# msp430g2553o.net
KiCad netlist of a schematic drawn in Altium Designer
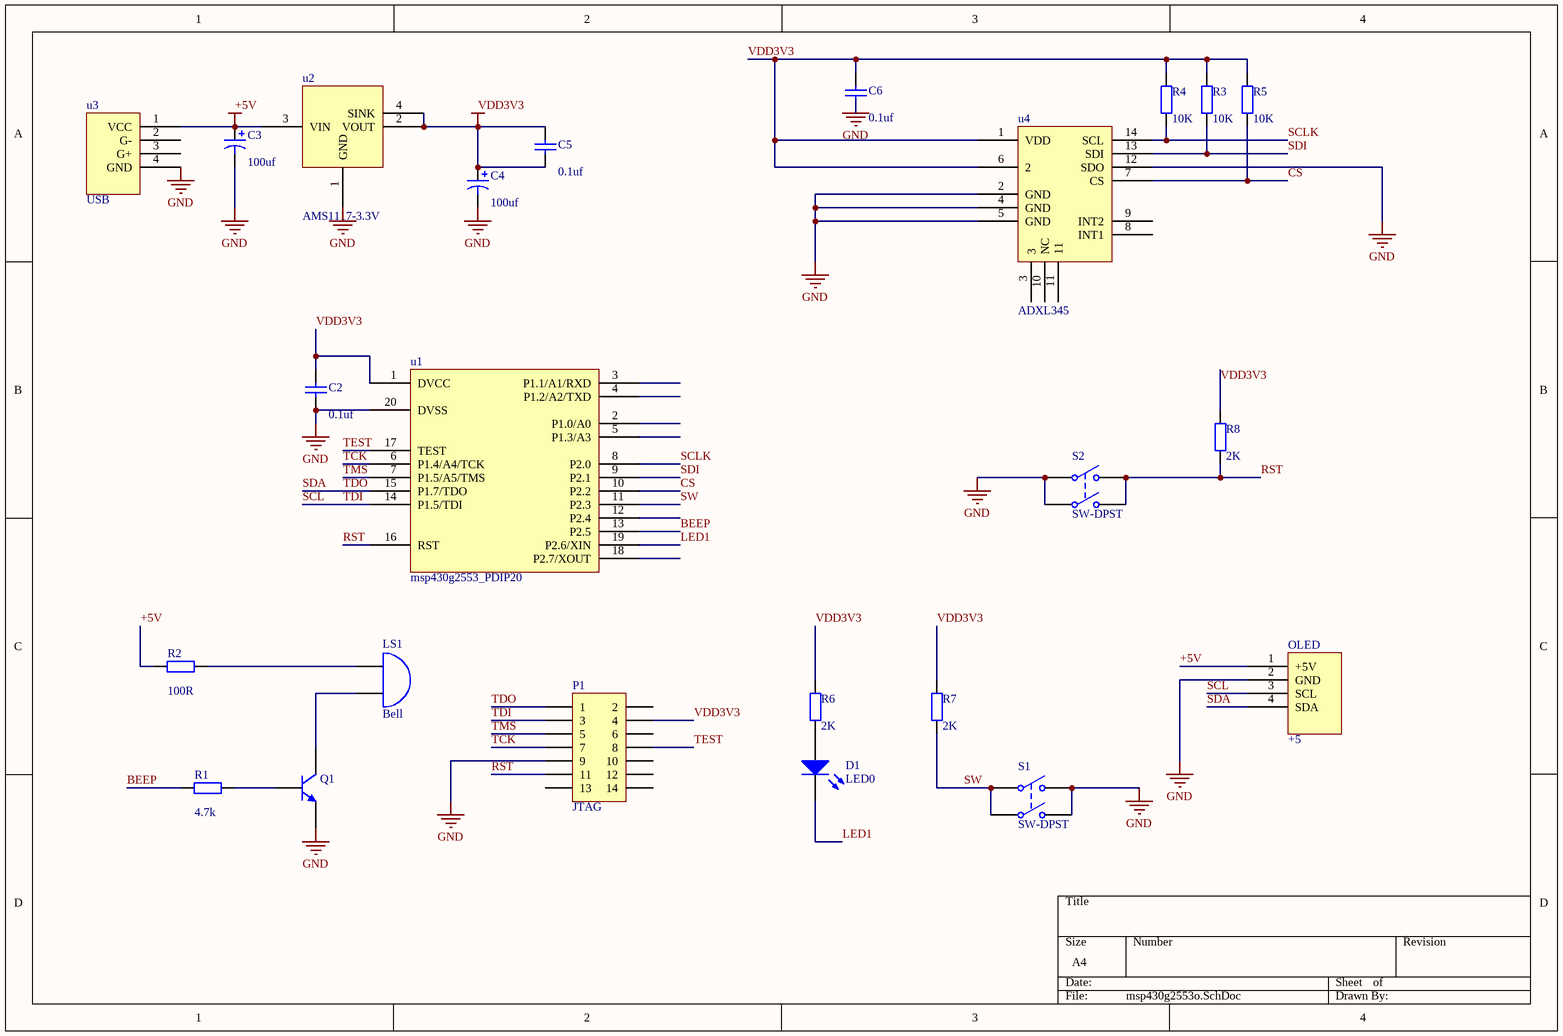
[diagram p0: msp430g2553o.SchDoc]

(export (version "E")
  (design (tool "Eeschema 10.0.6"))
  (components
    (comp (ref "C2")
      (value "0.1uf")
      (footprint "6-0805_N")
      (description "Capacitor")
      (fields (field (name "Comment") "Cap") (field (name "PUBLISHER") "Altium Limited"))
      (libsource (lib "msp430g2553") (part "Cap"))
    )
    (comp (ref "C3")
      (value "100uf")
      (footprint "Cap2_polar")
      (description "Polarized Capacitor (Axial)")
      (fields (field (name "Comment") "Cap Pol2") (field (name "PUBLISHER") "Altium Limited"))
      (libsource (lib "msp430g2553") (part "Cap Pol2"))
    )
    (comp (ref "C4")
      (value "100uf")
      (footprint "Cap2_polar")
      (description "Polarized Capacitor (Axial)")
      (fields (field (name "Comment") "Cap Pol2") (field (name "PUBLISHER") "Altium Limited"))
      (libsource (lib "msp430g2553") (part "Cap Pol2"))
    )
    (comp (ref "C5")
      (value "0.1uf")
      (footprint "6-0805_N")
      (description "Capacitor")
      (fields (field (name "Comment") "Cap") (field (name "PUBLISHER") "Altium Limited"))
      (libsource (lib "msp430g2553") (part "Cap"))
    )
    (comp (ref "C6")
      (value "0.1uf")
      (footprint "6-0805_N")
      (description "Capacitor")
      (fields (field (name "Comment") "Cap") (field (name "PUBLISHER") "Altium Limited"))
      (libsource (lib "msp430g2553") (part "Cap"))
    )
    (comp (ref "D1")
      (value "LED0")
      (footprint "6-0805_N - duplicate")
      (description "Typical INFRARED GaAs LED")
      (fields (field (name "PUBLISHER") "Altium Limited"))
      (libsource (lib "msp430g2553") (part "LED0"))
    )
    (comp (ref "LS1")
      (value "Bell")
      (footprint "bell")
      (description "Electrical Bell")
      (fields (field (name "PUBLISHER") "Altium Limited"))
      (libsource (lib "msp430g2553") (part "Bell"))
    )
    (comp (ref "OLED") (value "+5") (footprint "OLED") (libsource (lib "msp430g2553") (part "OLED")))
    (comp (ref "P1")
      (value "JTAG")
      (footprint "HDR2X7H")
      (description "Header, 7-Pin, Dual row")
      (fields (field (name "PUBLISHER") "Altium Limited"))
      (libsource (lib "msp430g2553") (part "JTAG"))
    )
    (comp (ref "Q1")
      (value "NPN")
      (footprint "SOT23_N")
      (description "NPN Bipolar Transistor")
      (fields (field (name "PUBLISHER") "Altium Limited"))
      (libsource (lib "msp430g2553") (part "NPN"))
    )
    (comp (ref "R1")
      (value "4.7k")
      (footprint "6-0805_N")
      (description "Resistor")
      (fields (field (name "Comment") "Res2") (field (name "PUBLISHER") "Altium Limited"))
      (libsource (lib "") (part "Res2_1"))
    )
    (comp (ref "R2")
      (value "100R")
      (footprint "6-0805_N")
      (description "Resistor")
      (fields (field (name "Comment") "Res2") (field (name "PUBLISHER") "Altium Limited"))
      (libsource (lib "") (part "Res2_1"))
    )
    (comp (ref "R3")
      (value "10K")
      (footprint "6-0805_N")
      (description "Resistor")
      (fields (field (name "Comment") "Res2") (field (name "PUBLISHER") "Altium Limited"))
      (libsource (lib "msp430g2553") (part "Res2"))
    )
    (comp (ref "R4")
      (value "10K")
      (footprint "6-0805_N")
      (description "Resistor")
      (fields (field (name "Comment") "Res2") (field (name "PUBLISHER") "Altium Limited"))
      (libsource (lib "msp430g2553") (part "Res2"))
    )
    (comp (ref "R5")
      (value "10K")
      (footprint "6-0805_N")
      (description "Resistor")
      (fields (field (name "Comment") "Res2") (field (name "PUBLISHER") "Altium Limited"))
      (libsource (lib "msp430g2553") (part "Res2"))
    )
    (comp (ref "R6")
      (value "2K")
      (footprint "6-0805_N")
      (description "Resistor")
      (fields (field (name "Comment") "Res2") (field (name "PUBLISHER") "Altium Limited"))
      (libsource (lib "msp430g2553") (part "Res2"))
    )
    (comp (ref "R7")
      (value "2K")
      (footprint "6-0805_N")
      (description "Resistor")
      (fields (field (name "Comment") "Res2") (field (name "PUBLISHER") "Altium Limited"))
      (libsource (lib "msp430g2553") (part "Res2"))
    )
    (comp (ref "R8")
      (value "2K")
      (footprint "6-0805_N")
      (description "Resistor")
      (fields (field (name "Comment") "Res2") (field (name "PUBLISHER") "Altium Limited"))
      (libsource (lib "msp430g2553") (part "Res2"))
    )
    (comp (ref "S1")
      (value "SW-DPST")
      (footprint "DPST-4")
      (description "Double-Pole, Single-Throw Switch")
      (fields (field (name "PUBLISHER") "Altium Limited"))
      (libsource (lib "msp430g2553") (part "SW-DPST"))
    )
    (comp (ref "S2")
      (value "SW-DPST")
      (footprint "DPST-4")
      (description "Double-Pole, Single-Throw Switch")
      (fields (field (name "PUBLISHER") "Altium Limited"))
      (libsource (lib "msp430g2553") (part "SW-DPST"))
    )
    (comp (ref "u1")
      (value "msp430g2553_PDIP20")
      (footprint "DIP20")
      (libsource (lib "msp430g2553") (part "msp430g2553_PDIP20"))
    )
    (comp (ref "u2")
      (value "AMS1117-3.3V")
      (footprint "SOT223_N")
      (libsource (lib "msp430g2553") (part "AMS1117-3.3V"))
    )
    (comp (ref "u3") (value "USB") (footprint "USB2.5-2H4") (libsource (lib "msp430g2553") (part "USB")))
    (comp (ref "u4") (value "ADXL345") (footprint "ADXL345") (libsource (lib "msp430g2553") (part "ADXL345")))
  )
  (nets
    (net (code "1") (name "+5") (class "Default")
      (node (ref "C3") (pin "2") (pinfunction "2_2") (pintype "passive"))
      (node (ref "u2") (pin "3") (pinfunction "VIN_3") (pintype "passive"))
      (node (ref "u3") (pin "1") (pinfunction "VCC_1") (pintype "passive"))
    )
    (net (code "2") (name "/+5V") (class "Default")
      (node (ref "OLED") (pin "1") (pinfunction "+5V_1") (pintype "passive"))
      (node (ref "R2") (pin "1") (pinfunction "1_1") (pintype "passive"))
    )
    (net (code "3") (name "/BEEP") (class "Default")
      (node (ref "R1") (pin "1") (pinfunction "1_1") (pintype "passive"))
      (node (ref "u1") (pin "13") (pinfunction "P2.5_13") (pintype "passive"))
    )
    (net (code "4") (name "/CS") (class "Default")
      (node (ref "R5") (pin "1") (pinfunction "1_1") (pintype "passive"))
      (node (ref "u1") (pin "10") (pinfunction "P2.2_10") (pintype "passive"))
      (node (ref "u4") (pin "7") (pinfunction "CS_7") (pintype "passive"))
    )
    (net (code "5") (name "/LED1") (class "Default")
      (node (ref "D1") (pin "2") (pinfunction "K_2") (pintype "passive"))
      (node (ref "u1") (pin "19") (pinfunction "P2.6/XIN_19") (pintype "passive"))
    )
    (net (code "6") (name "/RST") (class "Default")
      (node (ref "P1") (pin "11") (pinfunction "11_11") (pintype "passive"))
      (node (ref "R8") (pin "1") (pinfunction "1_1") (pintype "passive"))
      (node (ref "S2") (pin "3") (pinfunction "NO1_3") (pintype "passive"))
      (node (ref "S2") (pin "4") (pinfunction "NO2_4") (pintype "passive"))
      (node (ref "u1") (pin "16") (pinfunction "RST_16") (pintype "passive"))
    )
    (net (code "7") (name "/SCL") (class "Default")
      (node (ref "OLED") (pin "3") (pinfunction "SCL_3") (pintype "passive"))
      (node (ref "P1") (pin "3") (pinfunction "3_3") (pintype "passive"))
      (node (ref "u1") (pin "14") (pinfunction "P1.5/TDI_14") (pintype "passive"))
    )
    (net (code "8") (name "/SCLK") (class "Default")
      (node (ref "R4") (pin "1") (pinfunction "1_1") (pintype "passive"))
      (node (ref "u1") (pin "8") (pinfunction "P2.0_8") (pintype "passive"))
      (node (ref "u4") (pin "14") (pinfunction "SCL_14") (pintype "passive"))
    )
    (net (code "9") (name "/SDA") (class "Default")
      (node (ref "OLED") (pin "4") (pinfunction "SDA_4") (pintype "passive"))
      (node (ref "P1") (pin "1") (pinfunction "1_1") (pintype "passive"))
      (node (ref "u1") (pin "15") (pinfunction "P1.7/TDO_15") (pintype "passive"))
    )
    (net (code "10") (name "/SDI") (class "Default")
      (node (ref "R3") (pin "1") (pinfunction "1_1") (pintype "passive"))
      (node (ref "u1") (pin "9") (pinfunction "P2.1_9") (pintype "passive"))
      (node (ref "u4") (pin "13") (pinfunction "SDI_13") (pintype "passive"))
    )
    (net (code "11") (name "/SW") (class "Default")
      (node (ref "R7") (pin "1") (pinfunction "1_1") (pintype "passive"))
      (node (ref "S1") (pin "1") (pinfunction "COMMON1_1") (pintype "passive"))
      (node (ref "S1") (pin "2") (pinfunction "COMMON2_2") (pintype "passive"))
      (node (ref "u1") (pin "11") (pinfunction "P2.3_11") (pintype "passive"))
    )
    (net (code "12") (name "/TCK") (class "Default")
      (node (ref "P1") (pin "7") (pinfunction "7_7") (pintype "passive"))
      (node (ref "u1") (pin "6") (pinfunction "P1.4/A4/TCK_6") (pintype "passive"))
    )
    (net (code "13") (name "/TEST") (class "Default")
      (node (ref "P1") (pin "8") (pinfunction "8_8") (pintype "passive"))
      (node (ref "u1") (pin "17") (pinfunction "TEST_17") (pintype "passive"))
    )
    (net (code "14") (name "/TMS") (class "Default")
      (node (ref "P1") (pin "5") (pinfunction "5_5") (pintype "passive"))
      (node (ref "u1") (pin "7") (pinfunction "P1.5/A5/TMS_7") (pintype "passive"))
    )
    (net (code "15") (name "/VDD3V3") (class "Default")
      (node (ref "C2") (pin "2") (pinfunction "2_2") (pintype "passive"))
      (node (ref "C6") (pin "2") (pinfunction "2_2") (pintype "passive"))
      (node (ref "P1") (pin "4") (pinfunction "4_4") (pintype "passive"))
      (node (ref "R3") (pin "2") (pinfunction "2_2") (pintype "passive"))
      (node (ref "R4") (pin "2") (pinfunction "2_2") (pintype "passive"))
      (node (ref "R5") (pin "2") (pinfunction "2_2") (pintype "passive"))
      (node (ref "R6") (pin "2") (pinfunction "2_2") (pintype "passive"))
      (node (ref "R7") (pin "2") (pinfunction "2_2") (pintype "passive"))
      (node (ref "R8") (pin "2") (pinfunction "2_2") (pintype "passive"))
      (node (ref "u1") (pin "1") (pinfunction "DVCC_1") (pintype "passive"))
      (node (ref "u4") (pin "1") (pinfunction "VDD_1") (pintype "passive"))
      (node (ref "u4") (pin "6") (pinfunction "2_6") (pintype "passive"))
    )
    (net (code "16") (name "3.3") (class "Default")
      (node (ref "C4") (pin "2") (pinfunction "2_2") (pintype "passive"))
      (node (ref "C5") (pin "1") (pinfunction "1_1") (pintype "passive"))
      (node (ref "C5") (pin "2") (pinfunction "2_2") (pintype "passive"))
      (node (ref "u2") (pin "2") (pinfunction "VOUT_2") (pintype "passive"))
      (node (ref "u2") (pin "4") (pinfunction "SINK_4") (pintype "passive"))
    )
    (net (code "17") (name "GND") (class "Default")
      (node (ref "C2") (pin "1") (pinfunction "1_1") (pintype "passive"))
      (node (ref "C3") (pin "1") (pinfunction "1_1") (pintype "passive"))
      (node (ref "C4") (pin "1") (pinfunction "1_1") (pintype "passive"))
      (node (ref "C6") (pin "1") (pinfunction "1_1") (pintype "passive"))
      (node (ref "OLED") (pin "2") (pinfunction "GND_2") (pintype "passive"))
      (node (ref "P1") (pin "9") (pinfunction "9_9") (pintype "passive"))
      (node (ref "Q1") (pin "3") (pinfunction "E_3") (pintype "passive"))
      (node (ref "S1") (pin "3") (pinfunction "NO1_3") (pintype "passive"))
      (node (ref "S1") (pin "4") (pinfunction "NO2_4") (pintype "passive"))
      (node (ref "S2") (pin "1") (pinfunction "COMMON1_1") (pintype "passive"))
      (node (ref "S2") (pin "2") (pinfunction "COMMON2_2") (pintype "passive"))
      (node (ref "u1") (pin "20") (pinfunction "DVSS_20") (pintype "passive"))
      (node (ref "u2") (pin "1") (pinfunction "GND_1") (pintype "passive"))
      (node (ref "u3") (pin "4") (pinfunction "GND_4") (pintype "passive"))
      (node (ref "u4") (pin "12") (pinfunction "SDO_12") (pintype "passive"))
      (node (ref "u4") (pin "2") (pinfunction "GND_2") (pintype "passive"))
      (node (ref "u4") (pin "4") (pinfunction "GND_4") (pintype "passive"))
      (node (ref "u4") (pin "5") (pinfunction "GND_5") (pintype "passive"))
    )
    (net (code "18") (name "Net-(D1-A)") (class "Default")
      (node (ref "D1") (pin "1") (pinfunction "A_1") (pintype "passive"))
      (node (ref "R6") (pin "1") (pinfunction "1_1") (pintype "passive"))
    )
    (net (code "19") (name "Net-(LS1-A)") (class "Default")
      (node (ref "LS1") (pin "1") (pinfunction "A_1") (pintype "passive"))
      (node (ref "R2") (pin "2") (pinfunction "2_2") (pintype "passive"))
    )
    (net (code "20") (name "Net-(LS1-B)") (class "Default")
      (node (ref "LS1") (pin "2") (pinfunction "B_2") (pintype "passive"))
      (node (ref "Q1") (pin "1") (pinfunction "C_1") (pintype "passive"))
    )
    (net (code "21") (name "Net-(Q1-B)") (class "Default")
      (node (ref "Q1") (pin "2") (pinfunction "B_2") (pintype "passive"))
      (node (ref "R1") (pin "2") (pinfunction "2_2") (pintype "passive"))
    )
    (net (code "22") (name "unconnected-(P1-Pad2)") (class "Default")
      (node (ref "P1") (pin "2") (pinfunction "2_2") (pintype "passive"))
    )
    (net (code "23") (name "unconnected-(P1-Pad6)") (class "Default")
      (node (ref "P1") (pin "6") (pinfunction "6_6") (pintype "passive"))
    )
    (net (code "24") (name "unconnected-(P1-Pad10)") (class "Default")
      (node (ref "P1") (pin "10") (pinfunction "10_10") (pintype "passive"))
    )
    (net (code "25") (name "unconnected-(P1-Pad12)") (class "Default")
      (node (ref "P1") (pin "12") (pinfunction "12_12") (pintype "passive"))
    )
    (net (code "26") (name "unconnected-(P1-Pad13)") (class "Default")
      (node (ref "P1") (pin "13") (pinfunction "13_13") (pintype "passive"))
    )
    (net (code "27") (name "unconnected-(P1-Pad14)") (class "Default")
      (node (ref "P1") (pin "14") (pinfunction "14_14") (pintype "passive"))
    )
    (net (code "28") (name "unconnected-(u1-P1.0{slash}A0-Pad2)") (class "Default")
      (node (ref "u1") (pin "2") (pinfunction "P1.0/A0_2") (pintype "passive"))
    )
    (net (code "29") (name "unconnected-(u1-P1.1{slash}A1{slash}RXD-Pad3)") (class "Default")
      (node (ref "u1") (pin "3") (pinfunction "P1.1/A1/RXD_3") (pintype "passive"))
    )
    (net (code "30") (name "unconnected-(u1-P1.2{slash}A2{slash}TXD-Pad4)") (class "Default")
      (node (ref "u1") (pin "4") (pinfunction "P1.2/A2/TXD_4") (pintype "passive"))
    )
    (net (code "31") (name "unconnected-(u1-P1.3{slash}A3-Pad5)") (class "Default")
      (node (ref "u1") (pin "5") (pinfunction "P1.3/A3_5") (pintype "passive"))
    )
    (net (code "32") (name "unconnected-(u1-P2.4-Pad12)") (class "Default")
      (node (ref "u1") (pin "12") (pinfunction "P2.4_12") (pintype "passive"))
    )
    (net (code "33") (name "unconnected-(u1-P2.7{slash}XOUT-Pad18)") (class "Default")
      (node (ref "u1") (pin "18") (pinfunction "P2.7/XOUT_18") (pintype "passive"))
    )
    (net (code "34") (name "unconnected-(u3-G+-Pad3)") (class "Default")
      (node (ref "u3") (pin "3") (pinfunction "G+_3") (pintype "passive"))
    )
    (net (code "35") (name "unconnected-(u3-G--Pad2)") (class "Default")
      (node (ref "u3") (pin "2") (pinfunction "G-_2") (pintype "passive"))
    )
    (net (code "36") (name "unconnected-(u4-INT1-Pad8)") (class "Default")
      (node (ref "u4") (pin "8") (pinfunction "INT1_8") (pintype "passive"))
    )
    (net (code "37") (name "unconnected-(u4-INT2-Pad9)") (class "Default")
      (node (ref "u4") (pin "9") (pinfunction "INT2_9") (pintype "passive"))
    )
    (net (code "38") (name "unconnected-(u4-NC-Pad10)") (class "Default")
      (node (ref "u4") (pin "10") (pinfunction "NC_10") (pintype "passive"))
    )
    (net (code "39") (name "unconnected-(u4-Pad3)") (class "Default")
      (node (ref "u4") (pin "3") (pinfunction "3_3") (pintype "passive"))
    )
    (net (code "40") (name "unconnected-(u4-Pad11)") (class "Default")
      (node (ref "u4") (pin "11") (pinfunction "11_11") (pintype "passive"))
    )
  )
)
